# RF_load_2512.net
KiCad netlist of a schematic drawn in Altium Designer
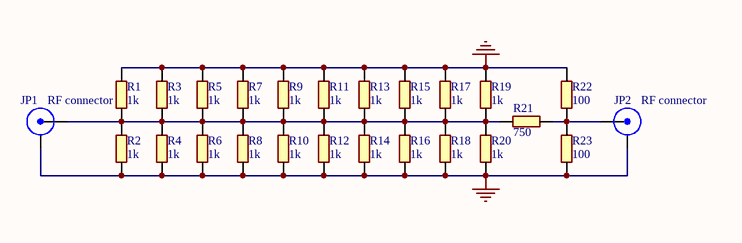
[diagram p0: RF_load_2512.SchDoc]

(export (version "E")
  (design (tool "Eeschema 10.0.6"))
  (components
    (comp (ref "JP1")
      (value "RF connector")
      (footprint "AMPHENOL_132357-11")
      (description "RF Connector")
      (libsource (lib "Connectors") (part "RF connector"))
    )
    (comp (ref "JP2")
      (value "RF connector")
      (footprint "AMPHENOL_132357-11")
      (description "RF Connector")
      (libsource (lib "Connectors") (part "RF connector"))
    )
    (comp (ref "R1") (value "1k") (footprint "R-2512_narrow") (libsource (lib "Passive") (part "RES")))
    (comp (ref "R2") (value "1k") (footprint "R-2512_narrow") (libsource (lib "Passive") (part "RES")))
    (comp (ref "R3") (value "1k") (footprint "R-2512_narrow") (libsource (lib "Passive") (part "RES")))
    (comp (ref "R4") (value "1k") (footprint "R-2512_narrow") (libsource (lib "Passive") (part "RES")))
    (comp (ref "R5") (value "1k") (footprint "R-2512_narrow") (libsource (lib "Passive") (part "RES")))
    (comp (ref "R6") (value "1k") (footprint "R-2512_narrow") (libsource (lib "Passive") (part "RES")))
    (comp (ref "R7") (value "1k") (footprint "R-2512_narrow") (libsource (lib "Passive") (part "RES")))
    (comp (ref "R8") (value "1k") (footprint "R-2512_narrow") (libsource (lib "Passive") (part "RES")))
    (comp (ref "R9") (value "1k") (footprint "R-2512_narrow") (libsource (lib "Passive") (part "RES")))
    (comp (ref "R10") (value "1k") (footprint "R-2512_narrow") (libsource (lib "Passive") (part "RES")))
    (comp (ref "R11") (value "1k") (footprint "R-2512_narrow") (libsource (lib "Passive") (part "RES")))
    (comp (ref "R12") (value "1k") (footprint "R-2512_narrow") (libsource (lib "Passive") (part "RES")))
    (comp (ref "R13") (value "1k") (footprint "R-2512_narrow") (libsource (lib "Passive") (part "RES")))
    (comp (ref "R14") (value "1k") (footprint "R-2512_narrow") (libsource (lib "Passive") (part "RES")))
    (comp (ref "R15") (value "1k") (footprint "R-2512_narrow") (libsource (lib "Passive") (part "RES")))
    (comp (ref "R16") (value "1k") (footprint "R-2512_narrow") (libsource (lib "Passive") (part "RES")))
    (comp (ref "R17") (value "1k") (footprint "R-2512_narrow") (libsource (lib "Passive") (part "RES")))
    (comp (ref "R18") (value "1k") (footprint "R-2512_narrow") (libsource (lib "Passive") (part "RES")))
    (comp (ref "R19") (value "1k") (footprint "R-2512_narrow") (libsource (lib "Passive") (part "RES")))
    (comp (ref "R20") (value "1k") (footprint "R-2512_narrow") (libsource (lib "Passive") (part "RES")))
    (comp (ref "R21") (value "750") (footprint "R-1206 _narrow") (libsource (lib "") (part "RES_1")))
    (comp (ref "R22") (value "100") (footprint "R-1206 _narrow") (libsource (lib "Passive") (part "RES")))
    (comp (ref "R23") (value "100") (footprint "R-1206 _narrow") (libsource (lib "Passive") (part "RES")))
  )
  (nets
    (net (code "1") (name "GND") (class "Default")
      (node (ref "JP1") (pin "2") (pinfunction "Y_2") (pintype "passive"))
      (node (ref "JP2") (pin "2") (pinfunction "Y_2") (pintype "passive"))
      (node (ref "R1") (pin "2") (pinfunction "2_2") (pintype "passive"))
      (node (ref "R10") (pin "1") (pinfunction "1_1") (pintype "passive"))
      (node (ref "R11") (pin "2") (pinfunction "2_2") (pintype "passive"))
      (node (ref "R12") (pin "1") (pinfunction "1_1") (pintype "passive"))
      (node (ref "R13") (pin "2") (pinfunction "2_2") (pintype "passive"))
      (node (ref "R14") (pin "1") (pinfunction "1_1") (pintype "passive"))
      (node (ref "R15") (pin "2") (pinfunction "2_2") (pintype "passive"))
      (node (ref "R16") (pin "1") (pinfunction "1_1") (pintype "passive"))
      (node (ref "R17") (pin "2") (pinfunction "2_2") (pintype "passive"))
      (node (ref "R18") (pin "1") (pinfunction "1_1") (pintype "passive"))
      (node (ref "R19") (pin "2") (pinfunction "2_2") (pintype "passive"))
      (node (ref "R2") (pin "1") (pinfunction "1_1") (pintype "passive"))
      (node (ref "R20") (pin "1") (pinfunction "1_1") (pintype "passive"))
      (node (ref "R22") (pin "2") (pinfunction "2_2") (pintype "passive"))
      (node (ref "R23") (pin "1") (pinfunction "1_1") (pintype "passive"))
      (node (ref "R3") (pin "2") (pinfunction "2_2") (pintype "passive"))
      (node (ref "R4") (pin "1") (pinfunction "1_1") (pintype "passive"))
      (node (ref "R5") (pin "2") (pinfunction "2_2") (pintype "passive"))
      (node (ref "R6") (pin "1") (pinfunction "1_1") (pintype "passive"))
      (node (ref "R7") (pin "2") (pinfunction "2_2") (pintype "passive"))
      (node (ref "R8") (pin "1") (pinfunction "1_1") (pintype "passive"))
      (node (ref "R9") (pin "2") (pinfunction "2_2") (pintype "passive"))
    )
    (net (code "2") (name "Net-(JP1-X)") (class "Default")
      (node (ref "JP1") (pin "1") (pinfunction "X_1") (pintype "passive"))
      (node (ref "R1") (pin "1") (pinfunction "1_1") (pintype "passive"))
      (node (ref "R10") (pin "2") (pinfunction "2_2") (pintype "passive"))
      (node (ref "R11") (pin "1") (pinfunction "1_1") (pintype "passive"))
      (node (ref "R12") (pin "2") (pinfunction "2_2") (pintype "passive"))
      (node (ref "R13") (pin "1") (pinfunction "1_1") (pintype "passive"))
      (node (ref "R14") (pin "2") (pinfunction "2_2") (pintype "passive"))
      (node (ref "R15") (pin "1") (pinfunction "1_1") (pintype "passive"))
      (node (ref "R16") (pin "2") (pinfunction "2_2") (pintype "passive"))
      (node (ref "R17") (pin "1") (pinfunction "1_1") (pintype "passive"))
      (node (ref "R18") (pin "2") (pinfunction "2_2") (pintype "passive"))
      (node (ref "R19") (pin "1") (pinfunction "1_1") (pintype "passive"))
      (node (ref "R2") (pin "2") (pinfunction "2_2") (pintype "passive"))
      (node (ref "R20") (pin "2") (pinfunction "2_2") (pintype "passive"))
      (node (ref "R21") (pin "2") (pinfunction "2_2") (pintype "passive"))
      (node (ref "R3") (pin "1") (pinfunction "1_1") (pintype "passive"))
      (node (ref "R4") (pin "2") (pinfunction "2_2") (pintype "passive"))
      (node (ref "R5") (pin "1") (pinfunction "1_1") (pintype "passive"))
      (node (ref "R6") (pin "2") (pinfunction "2_2") (pintype "passive"))
      (node (ref "R7") (pin "1") (pinfunction "1_1") (pintype "passive"))
      (node (ref "R8") (pin "2") (pinfunction "2_2") (pintype "passive"))
      (node (ref "R9") (pin "1") (pinfunction "1_1") (pintype "passive"))
    )
    (net (code "3") (name "Net-(JP2-X)") (class "Default")
      (node (ref "JP2") (pin "1") (pinfunction "X_1") (pintype "passive"))
      (node (ref "R21") (pin "1") (pinfunction "1_1") (pintype "passive"))
      (node (ref "R22") (pin "1") (pinfunction "1_1") (pintype "passive"))
      (node (ref "R23") (pin "2") (pinfunction "2_2") (pintype "passive"))
    )
  )
)
